# projeto.net
KiCad netlist of a schematic drawn in EasyEDA Pro
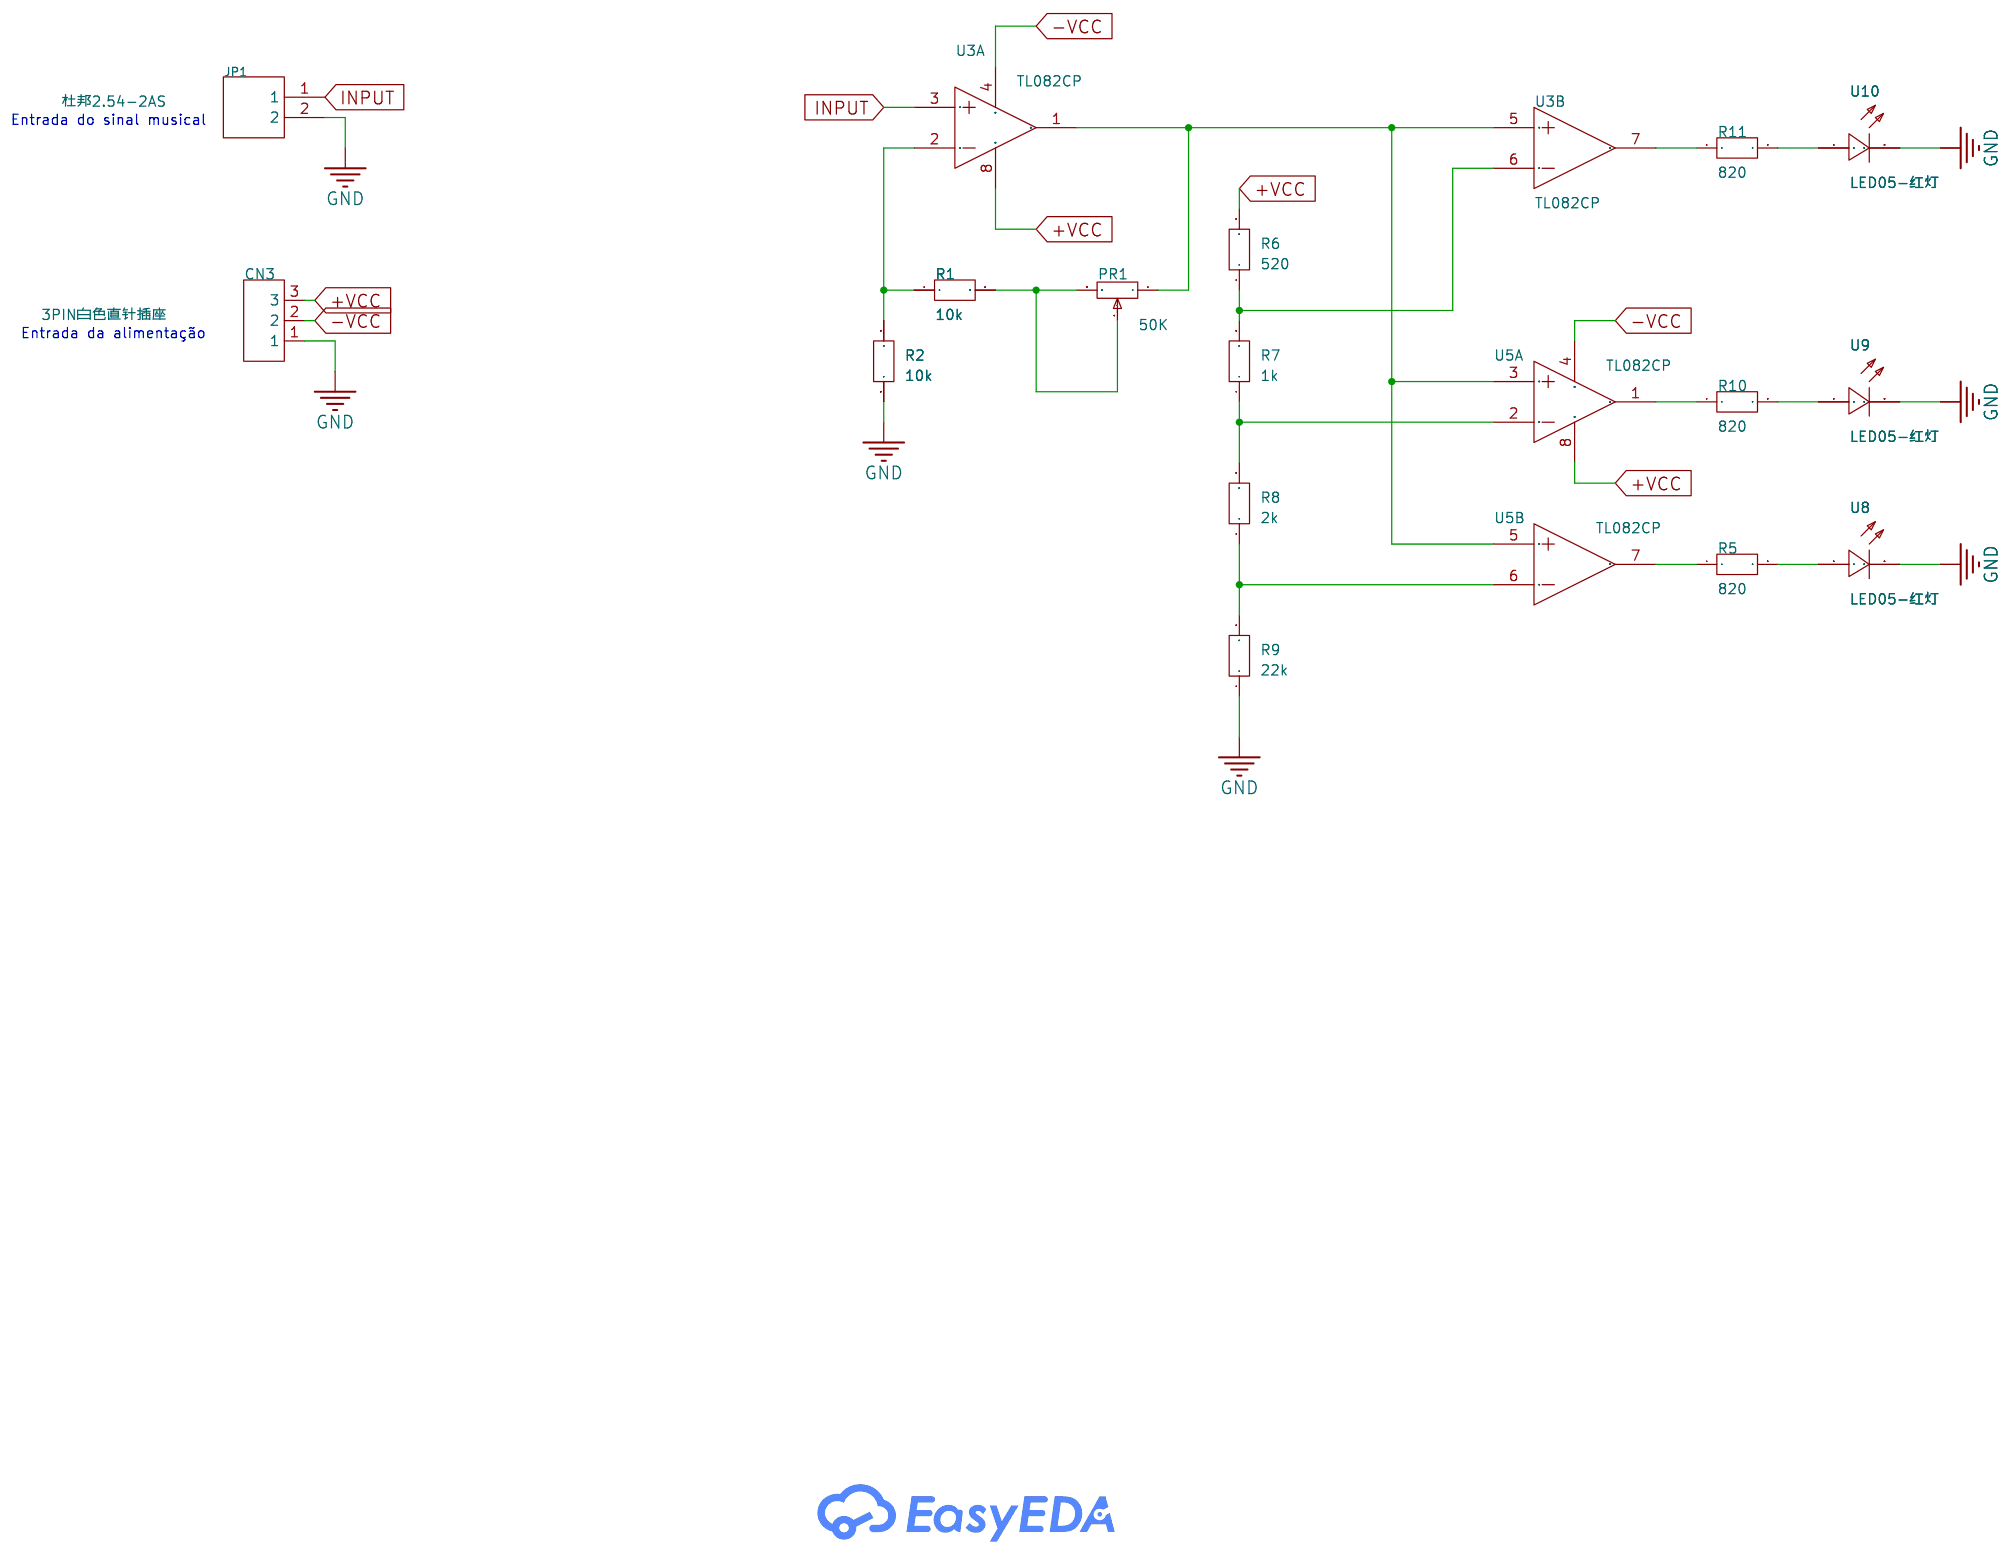
[diagram p0: schematic sheet]

(export (version "E")
  (design (tool "Eeschema 10.0.6"))
  (components
    (comp (ref "CN3")
      (value "3PIN白色直针插座")
      (footprint "easyedapro:CONN-TH_3P-P2.50_3PIN")
      (libsource (lib "easyedapro") (part "3PIN白色直针插座"))
    )
    (comp (ref "JP1")
      (value "杜邦2.54-2AS")
      (footprint "easyedapro:CONN-TH_2P-L7.6-W6.0-P2.54-V")
      (fields (field (name "Manufacturer") "BOOMELE(博穆精密)"))
      (libsource (lib "easyedapro") (part "2PDuPont with lock/"))
    )
    (comp (ref "PR1")
      (value "50K")
      (footprint "easyedapro:RES-ADJ-TH_3P-L9.5-W9.5-P2.54-BR-BS")
      (libsource (lib "easyedapro") (part "3386P-1-103LF"))
    )
    (comp (ref "R1")
      (value "10k")
      (footprint "easyedapro:RES-TH_BD4.5-L11.5-P15.50-D0.7")
      (fields
        (field (name "Manufacturer Part") "MOR02SJ075KA10")
        (field (name "Manufacturer") "UNI-ROYAL(厚声)")
      )
      (libsource (lib "easyedapro") (part "MOR02SJ075KA10"))
    )
    (comp (ref "R2")
      (value "10k")
      (footprint "easyedapro:RES-TH_BD4.5-L11.5-P15.50-D0.7")
      (fields
        (field (name "Manufacturer Part") "MOR02SJ075KA10")
        (field (name "Manufacturer") "UNI-ROYAL(厚声)")
      )
      (libsource (lib "easyedapro") (part "MOR02SJ075KA10"))
    )
    (comp (ref "R5")
      (value "820")
      (footprint "easyedapro:RES-TH_BD4.5-L11.5-P15.50-D0.7")
      (fields
        (field (name "Manufacturer Part") "MOR02SJ075KA10")
        (field (name "Manufacturer") "UNI-ROYAL(厚声)")
      )
      (libsource (lib "easyedapro") (part "MOR02SJ075KA10"))
    )
    (comp (ref "R6")
      (value "520")
      (footprint "easyedapro:RES-TH_BD4.5-L11.5-P15.50-D0.7")
      (fields
        (field (name "Manufacturer Part") "MOR02SJ075KA10")
        (field (name "Manufacturer") "UNI-ROYAL(厚声)")
      )
      (libsource (lib "easyedapro") (part "MOR02SJ075KA10"))
    )
    (comp (ref "R7")
      (value "1k")
      (footprint "easyedapro:RES-TH_BD4.5-L11.5-P15.50-D0.7")
      (fields
        (field (name "Manufacturer Part") "MOR02SJ075KA10")
        (field (name "Manufacturer") "UNI-ROYAL(厚声)")
      )
      (libsource (lib "easyedapro") (part "MOR02SJ075KA10"))
    )
    (comp (ref "R8")
      (value "2k")
      (footprint "easyedapro:RES-TH_BD4.5-L11.5-P15.50-D0.7")
      (fields
        (field (name "Manufacturer Part") "MOR02SJ075KA10")
        (field (name "Manufacturer") "UNI-ROYAL(厚声)")
      )
      (libsource (lib "easyedapro") (part "MOR02SJ075KA10"))
    )
    (comp (ref "R9")
      (value "22k")
      (footprint "easyedapro:RES-TH_BD4.5-L11.5-P15.50-D0.7")
      (fields
        (field (name "Manufacturer Part") "MOR02SJ075KA10")
        (field (name "Manufacturer") "UNI-ROYAL(厚声)")
      )
      (libsource (lib "easyedapro") (part "MOR02SJ075KA10"))
    )
    (comp (ref "R10")
      (value "820")
      (footprint "easyedapro:RES-TH_BD4.5-L11.5-P15.50-D0.7")
      (fields
        (field (name "Manufacturer Part") "MOR02SJ075KA10")
        (field (name "Manufacturer") "UNI-ROYAL(厚声)")
      )
      (libsource (lib "easyedapro") (part "MOR02SJ075KA10"))
    )
    (comp (ref "R11")
      (value "820")
      (footprint "easyedapro:RES-TH_BD4.5-L11.5-P15.50-D0.7")
      (fields
        (field (name "Manufacturer Part") "MOR02SJ075KA10")
        (field (name "Manufacturer") "UNI-ROYAL(厚声)")
      )
      (libsource (lib "easyedapro") (part "MOR02SJ075KA10"))
    )
    (comp (ref "U3")
      (value "TL082CP")
      (footprint "easyedapro:PDIP-8_L9.6-W6.4-P2.54-LS7.6-BL")
      (fields (field (name "Manufacturer") "TI(德州仪器)"))
      (libsource (lib "easyedapro") (part "TL082CP"))
    )
    (comp (ref "U5")
      (value "TL082CP")
      (footprint "easyedapro:PDIP-8_L9.6-W6.4-P2.54-LS7.6-BL")
      (fields (field (name "Manufacturer") "TI(德州仪器)"))
      (libsource (lib "easyedapro") (part "TL082CP"))
    )
    (comp (ref "U8")
      (value "LED05-红灯")
      (footprint "easyedapro:LED-TH_LED-3MM_RED")
      (libsource (lib "easyedapro") (part "LED05-红灯"))
    )
    (comp (ref "U9")
      (value "LED05-红灯")
      (footprint "easyedapro:LED-TH_LED-3MM_RED")
      (libsource (lib "easyedapro") (part "LED05-红灯"))
    )
    (comp (ref "U10")
      (value "LED05-红灯")
      (footprint "easyedapro:LED-TH_LED-3MM_RED")
      (libsource (lib "easyedapro") (part "LED05-红灯"))
    )
  )
  (nets
    (net (code "1") (name "+VCC") (class "Default")
      (node (ref "CN3") (pin "3") (pinfunction "3_3") (pintype "unspecified"))
      (node (ref "R6") (pin "2") (pinfunction "2_2") (pintype "unspecified"))
      (node (ref "U3") (pin "8") (pinfunction "VCC+_8") (pintype "unspecified"))
      (node (ref "U5") (pin "8") (pinfunction "VCC+_8") (pintype "unspecified"))
    )
    (net (code "2") (name "-VCC") (class "Default")
      (node (ref "CN3") (pin "2") (pinfunction "2_2") (pintype "unspecified"))
      (node (ref "U3") (pin "4") (pinfunction "VCC-_4") (pintype "unspecified"))
      (node (ref "U5") (pin "4") (pinfunction "VCC-_4") (pintype "unspecified"))
    )
    (net (code "3") (name "GND") (class "Default")
      (node (ref "CN3") (pin "1") (pinfunction "1_1") (pintype "unspecified"))
      (node (ref "JP1") (pin "2") (pinfunction "2_2") (pintype "input"))
      (node (ref "R2") (pin "1") (pinfunction "1_1") (pintype "unspecified"))
      (node (ref "R9") (pin "1") (pinfunction "1_1") (pintype "unspecified"))
      (node (ref "U10") (pin "2") (pinfunction "2_2") (pintype "unspecified"))
      (node (ref "U8") (pin "2") (pinfunction "2_2") (pintype "unspecified"))
      (node (ref "U9") (pin "2") (pinfunction "2_2") (pintype "unspecified"))
    )
    (net (code "4") (name "INPUT") (class "Default")
      (node (ref "JP1") (pin "1") (pinfunction "1_1") (pintype "input"))
      (node (ref "U3") (pin "3") (pinfunction "IN1+_3") (pintype "unspecified"))
    )
    (net (code "5") (name "Net-(PR1-Pad2)") (class "Default")
      (node (ref "PR1") (pin "2") (pinfunction "2_2") (pintype "input"))
      (node (ref "PR1") (pin "3") (pinfunction "3_3") (pintype "input"))
      (node (ref "R1") (pin "2") (pinfunction "2_2") (pintype "unspecified"))
    )
    (net (code "6") (name "Net-(R5-Pad2)") (class "Default")
      (node (ref "R5") (pin "2") (pinfunction "2_2") (pintype "unspecified"))
      (node (ref "U8") (pin "1") (pinfunction "1_1") (pintype "unspecified"))
    )
    (net (code "7") (name "Net-(R10-Pad2)") (class "Default")
      (node (ref "R10") (pin "2") (pinfunction "2_2") (pintype "unspecified"))
      (node (ref "U9") (pin "1") (pinfunction "1_1") (pintype "unspecified"))
    )
    (net (code "8") (name "Net-(R11-Pad2)") (class "Default")
      (node (ref "R11") (pin "2") (pinfunction "2_2") (pintype "unspecified"))
      (node (ref "U10") (pin "1") (pinfunction "1_1") (pintype "unspecified"))
    )
    (net (code "9") (name "Net-(U3A-IN1-)") (class "Default")
      (node (ref "R1") (pin "1") (pinfunction "1_1") (pintype "unspecified"))
      (node (ref "R2") (pin "2") (pinfunction "2_2") (pintype "unspecified"))
      (node (ref "U3") (pin "2") (pinfunction "IN1-_2") (pintype "unspecified"))
    )
    (net (code "10") (name "Net-(U3A-OUT1)") (class "Default")
      (node (ref "PR1") (pin "1") (pinfunction "1_1") (pintype "input"))
      (node (ref "U3") (pin "1") (pinfunction "OUT1_1") (pintype "output"))
      (node (ref "U3") (pin "5") (pinfunction "IN2+_5") (pintype "unspecified"))
      (node (ref "U5") (pin "3") (pinfunction "IN1+_3") (pintype "unspecified"))
      (node (ref "U5") (pin "5") (pinfunction "IN2+_5") (pintype "unspecified"))
    )
    (net (code "11") (name "Net-(U3B-IN2-)") (class "Default")
      (node (ref "R6") (pin "1") (pinfunction "1_1") (pintype "unspecified"))
      (node (ref "R7") (pin "2") (pinfunction "2_2") (pintype "unspecified"))
      (node (ref "U3") (pin "6") (pinfunction "IN2-_6") (pintype "unspecified"))
    )
    (net (code "12") (name "Net-(U3B-OUT2)") (class "Default")
      (node (ref "R11") (pin "1") (pinfunction "1_1") (pintype "unspecified"))
      (node (ref "U3") (pin "7") (pinfunction "OUT2_7") (pintype "output"))
    )
    (net (code "13") (name "Net-(U5A-IN1-)") (class "Default")
      (node (ref "R7") (pin "1") (pinfunction "1_1") (pintype "unspecified"))
      (node (ref "R8") (pin "2") (pinfunction "2_2") (pintype "unspecified"))
      (node (ref "U5") (pin "2") (pinfunction "IN1-_2") (pintype "unspecified"))
    )
    (net (code "14") (name "Net-(U5A-OUT1)") (class "Default")
      (node (ref "R10") (pin "1") (pinfunction "1_1") (pintype "unspecified"))
      (node (ref "U5") (pin "1") (pinfunction "OUT1_1") (pintype "output"))
    )
    (net (code "15") (name "Net-(U5B-IN2-)") (class "Default")
      (node (ref "R8") (pin "1") (pinfunction "1_1") (pintype "unspecified"))
      (node (ref "R9") (pin "2") (pinfunction "2_2") (pintype "unspecified"))
      (node (ref "U5") (pin "6") (pinfunction "IN2-_6") (pintype "unspecified"))
    )
    (net (code "16") (name "Net-(U5B-OUT2)") (class "Default")
      (node (ref "R5") (pin "1") (pinfunction "1_1") (pintype "unspecified"))
      (node (ref "U5") (pin "7") (pinfunction "OUT2_7") (pintype "output"))
    )
  )
)
